# Connectors.net
KiCad netlist of a schematic drawn in Altium Designer
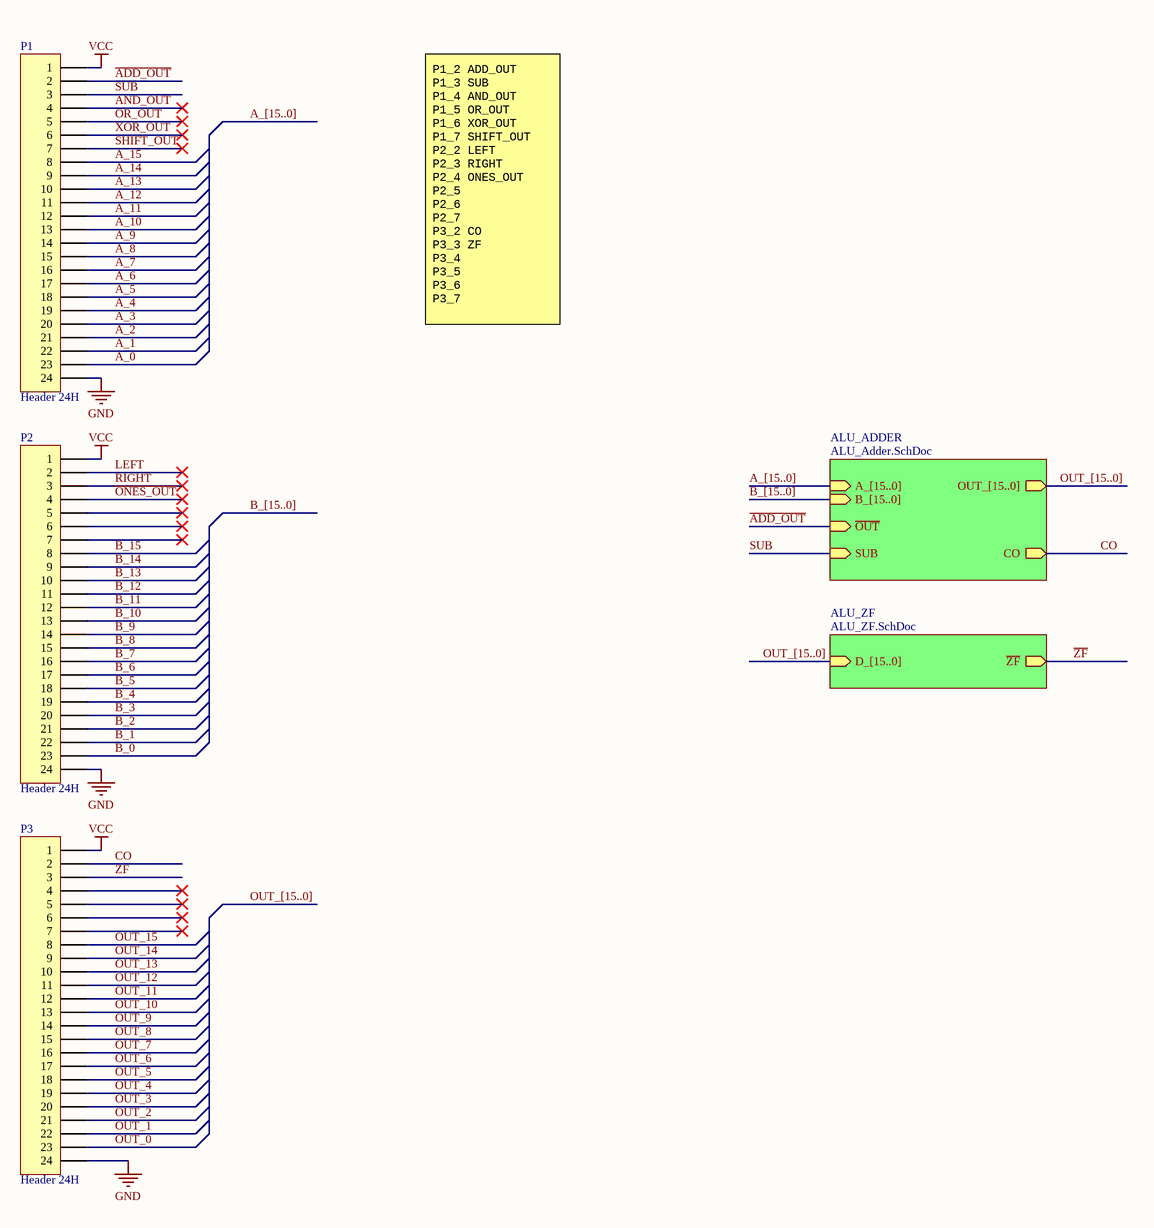
[diagram p0: Connectors.SchDoc]

(export (version "E")
  (design (tool "Eeschema 10.0.6"))
  (components
    (comp (ref "P1")
      (value "Header 24H")
      (footprint "HDR1X24H")
      (description "Header, 24-Pin, Right Angle")
      (fields (field (name "PUBLISHER") "Altium Limited"))
      (libsource (lib "Miscellaneous Connectors") (part "Header 24H"))
    )
    (comp (ref "P2")
      (value "Header 24H")
      (footprint "HDR1X24H")
      (description "Header, 24-Pin, Right Angle")
      (fields (field (name "PUBLISHER") "Altium Limited"))
      (libsource (lib "Miscellaneous Connectors") (part "Header 24H"))
    )
    (comp (ref "P3")
      (value "Header 24H")
      (footprint "HDR1X24H")
      (description "Header, 24-Pin, Right Angle")
      (fields (field (name "PUBLISHER") "Altium Limited"))
      (libsource (lib "Miscellaneous Connectors") (part "Header 24H"))
    )
  )
  (nets
    (net (code "1") (name "/A_0") (class "Default")
      (node (ref "P1") (pin "23") (pinfunction "23_23") (pintype "passive"))
    )
    (net (code "2") (name "/A_1") (class "Default")
      (node (ref "P1") (pin "22") (pinfunction "22_22") (pintype "passive"))
    )
    (net (code "3") (name "/A_2") (class "Default")
      (node (ref "P1") (pin "21") (pinfunction "21_21") (pintype "passive"))
    )
    (net (code "4") (name "/A_3") (class "Default")
      (node (ref "P1") (pin "20") (pinfunction "20_20") (pintype "passive"))
    )
    (net (code "5") (name "/A_4") (class "Default")
      (node (ref "P1") (pin "19") (pinfunction "19_19") (pintype "passive"))
    )
    (net (code "6") (name "/A_5") (class "Default")
      (node (ref "P1") (pin "18") (pinfunction "18_18") (pintype "passive"))
    )
    (net (code "7") (name "/A_6") (class "Default")
      (node (ref "P1") (pin "17") (pinfunction "17_17") (pintype "passive"))
    )
    (net (code "8") (name "/A_7") (class "Default")
      (node (ref "P1") (pin "16") (pinfunction "16_16") (pintype "passive"))
    )
    (net (code "9") (name "/A_8") (class "Default")
      (node (ref "P1") (pin "15") (pinfunction "15_15") (pintype "passive"))
    )
    (net (code "10") (name "/A_9") (class "Default")
      (node (ref "P1") (pin "14") (pinfunction "14_14") (pintype "passive"))
    )
    (net (code "11") (name "/A_10") (class "Default")
      (node (ref "P1") (pin "13") (pinfunction "13_13") (pintype "passive"))
    )
    (net (code "12") (name "/A_11") (class "Default")
      (node (ref "P1") (pin "12") (pinfunction "12_12") (pintype "passive"))
    )
    (net (code "13") (name "/A_12") (class "Default")
      (node (ref "P1") (pin "11") (pinfunction "11_11") (pintype "passive"))
    )
    (net (code "14") (name "/A_13") (class "Default")
      (node (ref "P1") (pin "10") (pinfunction "10_10") (pintype "passive"))
    )
    (net (code "15") (name "/A_14") (class "Default")
      (node (ref "P1") (pin "9") (pinfunction "9_9") (pintype "passive"))
    )
    (net (code "16") (name "/A_15") (class "Default")
      (node (ref "P1") (pin "8") (pinfunction "8_8") (pintype "passive"))
    )
    (net (code "18") (name "/B_0") (class "Default")
      (node (ref "P2") (pin "23") (pinfunction "23_23") (pintype "passive"))
    )
    (net (code "19") (name "/B_1") (class "Default")
      (node (ref "P2") (pin "22") (pinfunction "22_22") (pintype "passive"))
    )
    (net (code "20") (name "/B_2") (class "Default")
      (node (ref "P2") (pin "21") (pinfunction "21_21") (pintype "passive"))
    )
    (net (code "21") (name "/B_3") (class "Default")
      (node (ref "P2") (pin "20") (pinfunction "20_20") (pintype "passive"))
    )
    (net (code "22") (name "/B_4") (class "Default")
      (node (ref "P2") (pin "19") (pinfunction "19_19") (pintype "passive"))
    )
    (net (code "23") (name "/B_5") (class "Default")
      (node (ref "P2") (pin "18") (pinfunction "18_18") (pintype "passive"))
    )
    (net (code "24") (name "/B_6") (class "Default")
      (node (ref "P2") (pin "17") (pinfunction "17_17") (pintype "passive"))
    )
    (net (code "25") (name "/B_7") (class "Default")
      (node (ref "P2") (pin "16") (pinfunction "16_16") (pintype "passive"))
    )
    (net (code "26") (name "/B_8") (class "Default")
      (node (ref "P2") (pin "15") (pinfunction "15_15") (pintype "passive"))
    )
    (net (code "27") (name "/B_9") (class "Default")
      (node (ref "P2") (pin "14") (pinfunction "14_14") (pintype "passive"))
    )
    (net (code "28") (name "/B_10") (class "Default")
      (node (ref "P2") (pin "13") (pinfunction "13_13") (pintype "passive"))
    )
    (net (code "29") (name "/B_11") (class "Default")
      (node (ref "P2") (pin "12") (pinfunction "12_12") (pintype "passive"))
    )
    (net (code "30") (name "/B_12") (class "Default")
      (node (ref "P2") (pin "11") (pinfunction "11_11") (pintype "passive"))
    )
    (net (code "31") (name "/B_13") (class "Default")
      (node (ref "P2") (pin "10") (pinfunction "10_10") (pintype "passive"))
    )
    (net (code "32") (name "/B_14") (class "Default")
      (node (ref "P2") (pin "9") (pinfunction "9_9") (pintype "passive"))
    )
    (net (code "33") (name "/B_15") (class "Default")
      (node (ref "P2") (pin "8") (pinfunction "8_8") (pintype "passive"))
    )
    (net (code "35") (name "/CO") (class "Default")
      (node (ref "P3") (pin "2") (pinfunction "2_2") (pintype "passive"))
    )
    (net (code "36") (name "/LEFT") (class "Default")
      (node (ref "P2") (pin "2") (pinfunction "2_2") (pintype "passive+no_connect"))
    )
    (net (code "37") (name "/OUT_0") (class "Default")
      (node (ref "P3") (pin "23") (pinfunction "23_23") (pintype "passive"))
    )
    (net (code "38") (name "/OUT_1") (class "Default")
      (node (ref "P3") (pin "22") (pinfunction "22_22") (pintype "passive"))
    )
    (net (code "39") (name "/OUT_2") (class "Default")
      (node (ref "P3") (pin "21") (pinfunction "21_21") (pintype "passive"))
    )
    (net (code "40") (name "/OUT_3") (class "Default")
      (node (ref "P3") (pin "20") (pinfunction "20_20") (pintype "passive"))
    )
    (net (code "41") (name "/OUT_4") (class "Default")
      (node (ref "P3") (pin "19") (pinfunction "19_19") (pintype "passive"))
    )
    (net (code "42") (name "/OUT_5") (class "Default")
      (node (ref "P3") (pin "18") (pinfunction "18_18") (pintype "passive"))
    )
    (net (code "43") (name "/OUT_6") (class "Default")
      (node (ref "P3") (pin "17") (pinfunction "17_17") (pintype "passive"))
    )
    (net (code "44") (name "/OUT_7") (class "Default")
      (node (ref "P3") (pin "16") (pinfunction "16_16") (pintype "passive"))
    )
    (net (code "45") (name "/OUT_8") (class "Default")
      (node (ref "P3") (pin "15") (pinfunction "15_15") (pintype "passive"))
    )
    (net (code "46") (name "/OUT_9") (class "Default")
      (node (ref "P3") (pin "14") (pinfunction "14_14") (pintype "passive"))
    )
    (net (code "47") (name "/OUT_10") (class "Default")
      (node (ref "P3") (pin "13") (pinfunction "13_13") (pintype "passive"))
    )
    (net (code "48") (name "/OUT_11") (class "Default")
      (node (ref "P3") (pin "12") (pinfunction "12_12") (pintype "passive"))
    )
    (net (code "49") (name "/OUT_12") (class "Default")
      (node (ref "P3") (pin "11") (pinfunction "11_11") (pintype "passive"))
    )
    (net (code "50") (name "/OUT_13") (class "Default")
      (node (ref "P3") (pin "10") (pinfunction "10_10") (pintype "passive"))
    )
    (net (code "51") (name "/OUT_14") (class "Default")
      (node (ref "P3") (pin "9") (pinfunction "9_9") (pintype "passive"))
    )
    (net (code "52") (name "/OUT_15") (class "Default")
      (node (ref "P3") (pin "8") (pinfunction "8_8") (pintype "passive"))
    )
    (net (code "54") (name "/RIGHT") (class "Default")
      (node (ref "P2") (pin "3") (pinfunction "3_3") (pintype "passive+no_connect"))
    )
    (net (code "55") (name "/SUB") (class "Default")
      (node (ref "P1") (pin "3") (pinfunction "3_3") (pintype "passive"))
    )
    (net (code "56") (name "/~{ADD_OUT}") (class "Default")
      (node (ref "P1") (pin "2") (pinfunction "2_2") (pintype "passive"))
    )
    (net (code "57") (name "/~{AND_OUT}") (class "Default")
      (node (ref "P1") (pin "4") (pinfunction "4_4") (pintype "passive+no_connect"))
    )
    (net (code "58") (name "/~{ONES_OUT}") (class "Default")
      (node (ref "P2") (pin "4") (pinfunction "4_4") (pintype "passive+no_connect"))
    )
    (net (code "59") (name "/~{OR_OUT}") (class "Default")
      (node (ref "P1") (pin "5") (pinfunction "5_5") (pintype "passive+no_connect"))
    )
    (net (code "60") (name "/~{SHIFT_OUT}") (class "Default")
      (node (ref "P1") (pin "7") (pinfunction "7_7") (pintype "passive+no_connect"))
    )
    (net (code "61") (name "/~{XOR_OUT}") (class "Default")
      (node (ref "P1") (pin "6") (pinfunction "6_6") (pintype "passive+no_connect"))
    )
    (net (code "62") (name "/~{ZF}") (class "Default")
      (node (ref "P3") (pin "3") (pinfunction "3_3") (pintype "passive"))
    )
    (net (code "63") (name "GND") (class "Default")
      (node (ref "P1") (pin "24") (pinfunction "24_24") (pintype "passive"))
      (node (ref "P2") (pin "24") (pinfunction "24_24") (pintype "passive"))
      (node (ref "P3") (pin "24") (pinfunction "24_24") (pintype "passive"))
    )
    (net (code "64") (name "VCC") (class "Default")
      (node (ref "P1") (pin "1") (pinfunction "1_1") (pintype "passive"))
      (node (ref "P2") (pin "1") (pinfunction "1_1") (pintype "passive"))
      (node (ref "P3") (pin "1") (pinfunction "1_1") (pintype "passive"))
    )
    (net (code "65") (name "unconnected-(P2-Pad5)") (class "Default")
      (node (ref "P2") (pin "5") (pinfunction "5_5") (pintype "passive+no_connect"))
    )
    (net (code "66") (name "unconnected-(P2-Pad6)") (class "Default")
      (node (ref "P2") (pin "6") (pinfunction "6_6") (pintype "passive+no_connect"))
    )
    (net (code "67") (name "unconnected-(P2-Pad7)") (class "Default")
      (node (ref "P2") (pin "7") (pinfunction "7_7") (pintype "passive+no_connect"))
    )
    (net (code "68") (name "unconnected-(P3-Pad4)") (class "Default")
      (node (ref "P3") (pin "4") (pinfunction "4_4") (pintype "passive+no_connect"))
    )
    (net (code "69") (name "unconnected-(P3-Pad5)") (class "Default")
      (node (ref "P3") (pin "5") (pinfunction "5_5") (pintype "passive+no_connect"))
    )
    (net (code "70") (name "unconnected-(P3-Pad6)") (class "Default")
      (node (ref "P3") (pin "6") (pinfunction "6_6") (pintype "passive+no_connect"))
    )
    (net (code "71") (name "unconnected-(P3-Pad7)") (class "Default")
      (node (ref "P3") (pin "7") (pinfunction "7_7") (pintype "passive+no_connect"))
    )
  )
)
